# Sheet1.net
KiCad netlist of a schematic drawn in Altium Designer
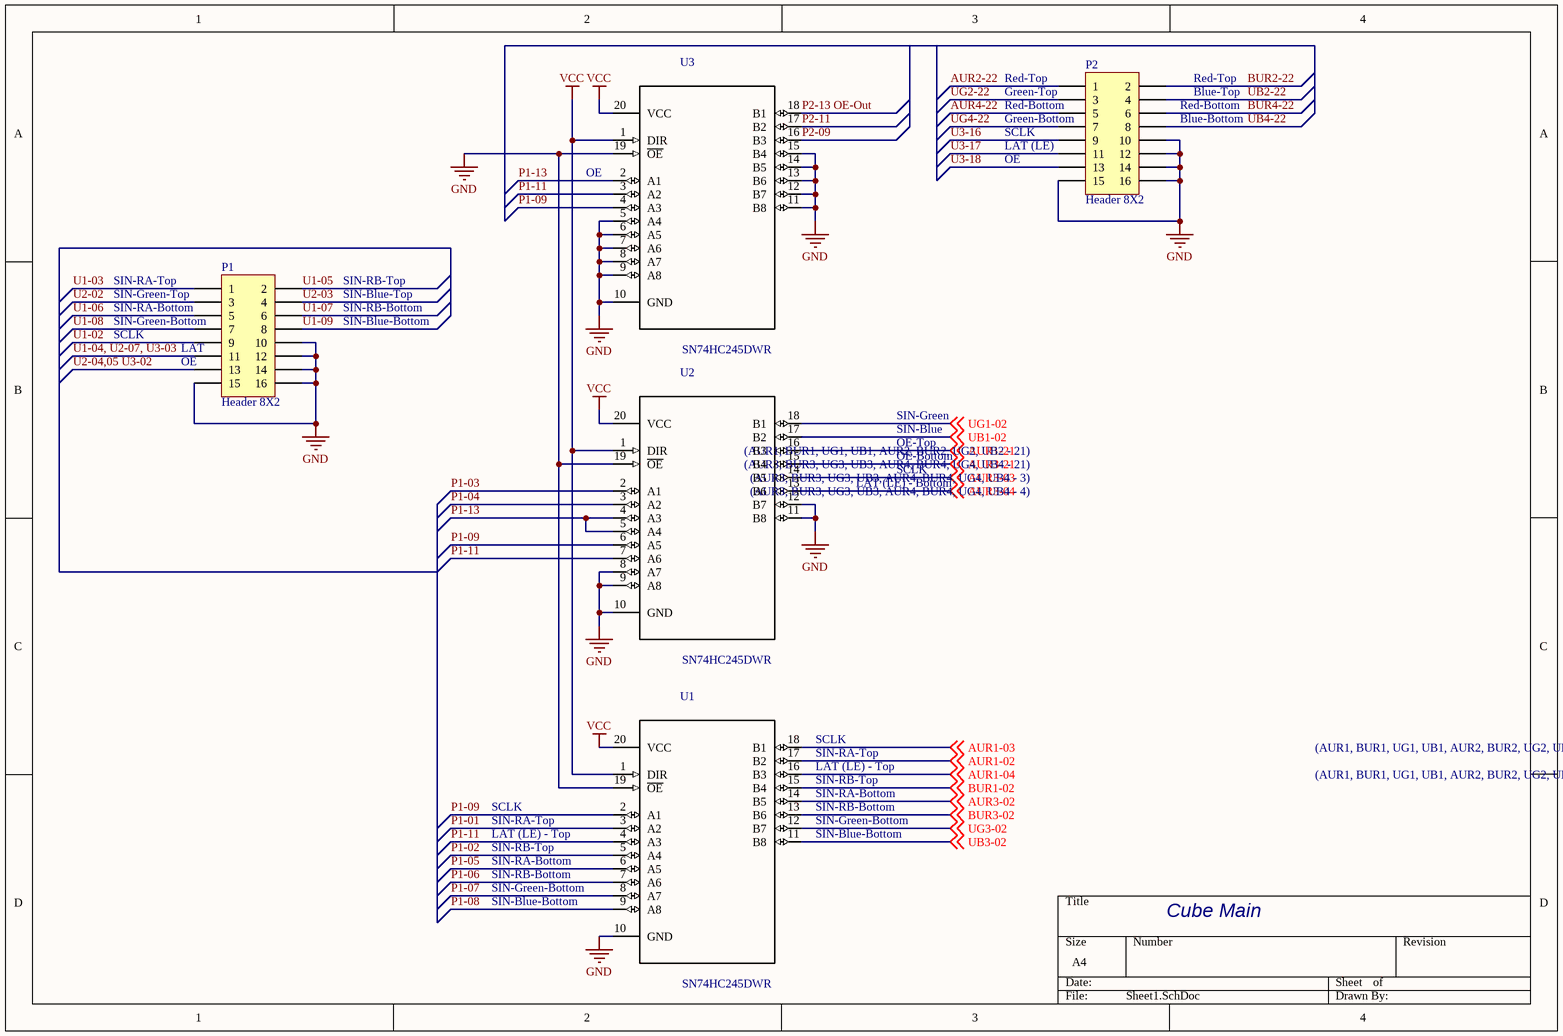
[diagram p0: Sheet1.SchDoc]

(export (version "E")
  (design (tool "Eeschema 10.0.6"))
  (components
    (comp (ref "P1")
      (value "Header 8X2")
      (footprint "HDR2X8")
      (description "Header, 8-Pin, Dual row")
      (fields (field (name "PUBLISHER") "Altium Limited"))
      (libsource (lib "Miscellaneous Connectors") (part "Header 8X2"))
    )
    (comp (ref "P2")
      (value "Header 8X2")
      (footprint "HDR2X8")
      (description "Header, 8-Pin, Dual row")
      (fields (field (name "PUBLISHER") "Altium Limited"))
      (libsource (lib "Miscellaneous Connectors") (part "Header 8X2"))
    )
    (comp (ref "U1")
      (value "SN74HC245DWR")
      (footprint "SOIC127P1030X265-20N")
      (description "Logic IC - Receiver, transceiver Texas Instruments SN74HC245DWR SOIC 20")
      (fields (field (name "MF") "Texas Instruments"))
      (libsource (lib "SN74HC245DWR") (part "SN74HC245DWR"))
    )
    (comp (ref "U2")
      (value "SN74HC245DWR")
      (footprint "SOIC127P1030X265-20N")
      (description "Logic IC - Receiver, transceiver Texas Instruments SN74HC245DWR SOIC 20")
      (fields (field (name "MF") "Texas Instruments"))
      (libsource (lib "SN74HC245DWR") (part "SN74HC245DWR"))
    )
    (comp (ref "U3")
      (value "SN74HC245DWR")
      (footprint "SOIC127P1030X265-20N")
      (description "Logic IC - Receiver, transceiver Texas Instruments SN74HC245DWR SOIC 20")
      (fields (field (name "MF") "Texas Instruments"))
      (libsource (lib "SN74HC245DWR") (part "SN74HC245DWR"))
    )
  )
  (nets
    (net (code "1") (name "/AUR2-22") (class "Default")
      (node (ref "P2") (pin "1") (pinfunction "1_1") (pintype "passive"))
    )
    (net (code "2") (name "/AUR4-22") (class "Default")
      (node (ref "P2") (pin "5") (pinfunction "5_5") (pintype "passive"))
    )
    (net (code "3") (name "/BUR2-22") (class "Default")
      (node (ref "P2") (pin "2") (pinfunction "2_2") (pintype "passive"))
    )
    (net (code "4") (name "/BUR4-22") (class "Default")
      (node (ref "P2") (pin "6") (pinfunction "6_6") (pintype "passive"))
    )
    (net (code "5") (name "/P1-01") (class "Default")
      (node (ref "U1") (pin "3") (pinfunction "A2_3") (pintype "bidirectional"))
    )
    (net (code "6") (name "/P1-02") (class "Default")
      (node (ref "U1") (pin "5") (pinfunction "A4_5") (pintype "bidirectional"))
    )
    (net (code "7") (name "/P1-03") (class "Default")
      (node (ref "U2") (pin "2") (pinfunction "A1_2") (pintype "bidirectional"))
    )
    (net (code "8") (name "/P1-04") (class "Default")
      (node (ref "U2") (pin "3") (pinfunction "A2_3") (pintype "bidirectional"))
    )
    (net (code "9") (name "/P1-05") (class "Default")
      (node (ref "U1") (pin "6") (pinfunction "A5_6") (pintype "bidirectional"))
    )
    (net (code "10") (name "/P1-06") (class "Default")
      (node (ref "U1") (pin "7") (pinfunction "A6_7") (pintype "bidirectional"))
    )
    (net (code "11") (name "/P1-07") (class "Default")
      (node (ref "U1") (pin "8") (pinfunction "A7_8") (pintype "bidirectional"))
    )
    (net (code "12") (name "/P1-08") (class "Default")
      (node (ref "U1") (pin "9") (pinfunction "A8_9") (pintype "bidirectional"))
    )
    (net (code "13") (name "/P1-09") (class "Default")
      (node (ref "U1") (pin "2") (pinfunction "A1_2") (pintype "bidirectional"))
      (node (ref "U2") (pin "6") (pinfunction "A5_6") (pintype "bidirectional"))
      (node (ref "U3") (pin "4") (pinfunction "A3_4") (pintype "bidirectional"))
    )
    (net (code "14") (name "/P1-11") (class "Default")
      (node (ref "U1") (pin "4") (pinfunction "A3_4") (pintype "bidirectional"))
      (node (ref "U2") (pin "7") (pinfunction "A6_7") (pintype "bidirectional"))
      (node (ref "U3") (pin "3") (pinfunction "A2_3") (pintype "bidirectional"))
    )
    (net (code "15") (name "/P1-13") (class "Default")
      (node (ref "U2") (pin "4") (pinfunction "A3_4") (pintype "bidirectional"))
      (node (ref "U2") (pin "5") (pinfunction "A4_5") (pintype "bidirectional"))
      (node (ref "U3") (pin "2") (pinfunction "A1_2") (pintype "bidirectional"))
    )
    (net (code "16") (name "/P2-09") (class "Default")
      (node (ref "U3") (pin "16") (pinfunction "B3_16") (pintype "bidirectional"))
    )
    (net (code "17") (name "/P2-11") (class "Default")
      (node (ref "U3") (pin "17") (pinfunction "B2_17") (pintype "bidirectional"))
    )
    (net (code "18") (name "/P2-13 OE-Out") (class "Default")
      (node (ref "U3") (pin "18") (pinfunction "B1_18") (pintype "bidirectional"))
    )
    (net (code "19") (name "/U1-02") (class "Default")
      (node (ref "P1") (pin "9") (pinfunction "9_9") (pintype "passive"))
    )
    (net (code "20") (name "/U1-03") (class "Default")
      (node (ref "P1") (pin "1") (pinfunction "1_1") (pintype "passive"))
    )
    (net (code "21") (name "/U1-04, U2-07, U3-03") (class "Default")
      (node (ref "P1") (pin "11") (pinfunction "11_11") (pintype "passive"))
    )
    (net (code "22") (name "/U1-05") (class "Default")
      (node (ref "P1") (pin "2") (pinfunction "2_2") (pintype "passive"))
    )
    (net (code "23") (name "/U1-06") (class "Default")
      (node (ref "P1") (pin "5") (pinfunction "5_5") (pintype "passive"))
    )
    (net (code "24") (name "/U1-07") (class "Default")
      (node (ref "P1") (pin "6") (pinfunction "6_6") (pintype "passive"))
    )
    (net (code "25") (name "/U1-08") (class "Default")
      (node (ref "P1") (pin "7") (pinfunction "7_7") (pintype "passive"))
    )
    (net (code "26") (name "/U1-09") (class "Default")
      (node (ref "P1") (pin "8") (pinfunction "8_8") (pintype "passive"))
    )
    (net (code "27") (name "/U2-02") (class "Default")
      (node (ref "P1") (pin "3") (pinfunction "3_3") (pintype "passive"))
    )
    (net (code "28") (name "/U2-03") (class "Default")
      (node (ref "P1") (pin "4") (pinfunction "4_4") (pintype "passive"))
    )
    (net (code "29") (name "/U2-04,05 U3-02") (class "Default")
      (node (ref "P1") (pin "13") (pinfunction "13_13") (pintype "passive"))
    )
    (net (code "30") (name "/U3-16") (class "Default")
      (node (ref "P2") (pin "9") (pinfunction "9_9") (pintype "passive"))
    )
    (net (code "31") (name "/U3-17") (class "Default")
      (node (ref "P2") (pin "11") (pinfunction "11_11") (pintype "passive"))
    )
    (net (code "32") (name "/U3-18") (class "Default")
      (node (ref "P2") (pin "13") (pinfunction "13_13") (pintype "passive"))
    )
    (net (code "33") (name "/UB2-22") (class "Default")
      (node (ref "P2") (pin "4") (pinfunction "4_4") (pintype "passive"))
    )
    (net (code "34") (name "/UB4-22") (class "Default")
      (node (ref "P2") (pin "8") (pinfunction "8_8") (pintype "passive"))
    )
    (net (code "35") (name "/UG2-22") (class "Default")
      (node (ref "P2") (pin "3") (pinfunction "3_3") (pintype "passive"))
    )
    (net (code "36") (name "/UG4-22") (class "Default")
      (node (ref "P2") (pin "7") (pinfunction "7_7") (pintype "passive"))
    )
    (net (code "37") (name "AUR1-02") (class "Default")
      (node (ref "U1") (pin "17") (pinfunction "B2_17") (pintype "bidirectional"))
    )
    (net (code "38") (name "AUR1-03") (class "Default")
      (node (ref "U1") (pin "18") (pinfunction "B1_18") (pintype "bidirectional"))
    )
    (net (code "39") (name "AUR1-04") (class "Default")
      (node (ref "U1") (pin "16") (pinfunction "B3_16") (pintype "bidirectional"))
    )
    (net (code "40") (name "AUR1-21") (class "Default")
      (node (ref "U2") (pin "16") (pinfunction "B3_16") (pintype "bidirectional"))
    )
    (net (code "41") (name "AUR3-02") (class "Default")
      (node (ref "U1") (pin "14") (pinfunction "B5_14") (pintype "bidirectional"))
    )
    (net (code "42") (name "AUR3-03") (class "Default")
      (node (ref "U2") (pin "14") (pinfunction "B5_14") (pintype "bidirectional"))
    )
    (net (code "43") (name "AUR3-04") (class "Default")
      (node (ref "U2") (pin "13") (pinfunction "B6_13") (pintype "bidirectional"))
    )
    (net (code "44") (name "AUR3-21") (class "Default")
      (node (ref "U2") (pin "15") (pinfunction "B4_15") (pintype "bidirectional"))
    )
    (net (code "45") (name "BUR1-02") (class "Default")
      (node (ref "U1") (pin "15") (pinfunction "B4_15") (pintype "bidirectional"))
    )
    (net (code "46") (name "BUR3-02") (class "Default")
      (node (ref "U1") (pin "13") (pinfunction "B6_13") (pintype "bidirectional"))
    )
    (net (code "47") (name "GND") (class "Default")
      (node (ref "P1") (pin "10") (pinfunction "10_10") (pintype "passive"))
      (node (ref "P1") (pin "12") (pinfunction "12_12") (pintype "passive"))
      (node (ref "P1") (pin "14") (pinfunction "14_14") (pintype "passive"))
      (node (ref "P1") (pin "15") (pinfunction "15_15") (pintype "passive"))
      (node (ref "P1") (pin "16") (pinfunction "16_16") (pintype "passive"))
      (node (ref "P2") (pin "10") (pinfunction "10_10") (pintype "passive"))
      (node (ref "P2") (pin "12") (pinfunction "12_12") (pintype "passive"))
      (node (ref "P2") (pin "14") (pinfunction "14_14") (pintype "passive"))
      (node (ref "P2") (pin "15") (pinfunction "15_15") (pintype "passive"))
      (node (ref "P2") (pin "16") (pinfunction "16_16") (pintype "passive"))
      (node (ref "U1") (pin "10") (pinfunction "GND_10") (pintype "passive"))
      (node (ref "U1") (pin "19") (pinfunction "~{OE}_19") (pintype "input"))
      (node (ref "U2") (pin "10") (pinfunction "GND_10") (pintype "passive"))
      (node (ref "U2") (pin "11") (pinfunction "B8_11") (pintype "bidirectional"))
      (node (ref "U2") (pin "12") (pinfunction "B7_12") (pintype "bidirectional"))
      (node (ref "U2") (pin "19") (pinfunction "~{OE}_19") (pintype "input"))
      (node (ref "U2") (pin "8") (pinfunction "A7_8") (pintype "bidirectional"))
      (node (ref "U2") (pin "9") (pinfunction "A8_9") (pintype "bidirectional"))
      (node (ref "U3") (pin "10") (pinfunction "GND_10") (pintype "passive"))
      (node (ref "U3") (pin "11") (pinfunction "B8_11") (pintype "bidirectional"))
      (node (ref "U3") (pin "12") (pinfunction "B7_12") (pintype "bidirectional"))
      (node (ref "U3") (pin "13") (pinfunction "B6_13") (pintype "bidirectional"))
      (node (ref "U3") (pin "14") (pinfunction "B5_14") (pintype "bidirectional"))
      (node (ref "U3") (pin "15") (pinfunction "B4_15") (pintype "bidirectional"))
      (node (ref "U3") (pin "19") (pinfunction "~{OE}_19") (pintype "input"))
      (node (ref "U3") (pin "5") (pinfunction "A4_5") (pintype "bidirectional"))
      (node (ref "U3") (pin "6") (pinfunction "A5_6") (pintype "bidirectional"))
      (node (ref "U3") (pin "7") (pinfunction "A6_7") (pintype "bidirectional"))
      (node (ref "U3") (pin "8") (pinfunction "A7_8") (pintype "bidirectional"))
      (node (ref "U3") (pin "9") (pinfunction "A8_9") (pintype "bidirectional"))
    )
    (net (code "48") (name "UB1-02") (class "Default")
      (node (ref "U2") (pin "17") (pinfunction "B2_17") (pintype "bidirectional"))
    )
    (net (code "49") (name "UB3-02") (class "Default")
      (node (ref "U1") (pin "11") (pinfunction "B8_11") (pintype "bidirectional"))
    )
    (net (code "50") (name "UG1-02") (class "Default")
      (node (ref "U2") (pin "18") (pinfunction "B1_18") (pintype "bidirectional"))
    )
    (net (code "51") (name "UG3-02") (class "Default")
      (node (ref "U1") (pin "12") (pinfunction "B7_12") (pintype "bidirectional"))
    )
    (net (code "52") (name "VCC") (class "Default")
      (node (ref "U1") (pin "1") (pinfunction "DIR_1") (pintype "input"))
      (node (ref "U1") (pin "20") (pinfunction "VCC_20") (pintype "power_in"))
      (node (ref "U2") (pin "1") (pinfunction "DIR_1") (pintype "input"))
      (node (ref "U2") (pin "20") (pinfunction "VCC_20") (pintype "power_in"))
      (node (ref "U3") (pin "1") (pinfunction "DIR_1") (pintype "input"))
      (node (ref "U3") (pin "20") (pinfunction "VCC_20") (pintype "power_in"))
    )
  )
)
